# lcdadapter.net
KiCad netlist of a schematic drawn in EAGLE
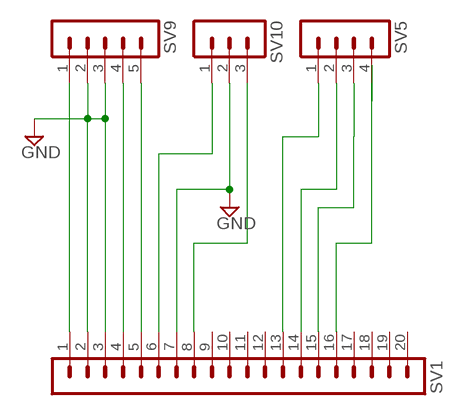
[diagram p0: schematic, sheet 1]

(export (version "E")
  (design (tool "Eeschema 10.0.6"))
  (components
    (comp (ref "SV1")
      (value "MA20-1L")
      (footprint "eagle-import:MA20-1L")
      (libsource (lib "eagle-import") (part "MA20-1L"))
    )
    (comp (ref "SV5")
      (value "MA04-1")
      (footprint "eagle-import:MA04-1")
      (libsource (lib "eagle-import") (part "MA04-1"))
    )
    (comp (ref "SV9")
      (value "MA05-1")
      (footprint "eagle-import:MA05-1")
      (libsource (lib "eagle-import") (part "MA05-1"))
    )
    (comp (ref "SV10")
      (value "MA03-1")
      (footprint "eagle-import:MA03-1")
      (libsource (lib "eagle-import") (part "MA03-1"))
    )
  )
  (nets
    (net (code "1") (name "GND") (class "Default")
      (node (ref "SV1") (pin "2") (pinfunction "2_2") (pintype "passive"))
      (node (ref "SV1") (pin "3") (pinfunction "3_3") (pintype "passive"))
      (node (ref "SV1") (pin "7") (pinfunction "7_7") (pintype "passive"))
      (node (ref "SV10") (pin "2") (pinfunction "2_2") (pintype "passive"))
      (node (ref "SV9") (pin "2") (pinfunction "2_2") (pintype "passive"))
      (node (ref "SV9") (pin "3") (pinfunction "3_3") (pintype "passive"))
    )
    (net (code "2") (name "Net-(SV1-Pad1)") (class "Default")
      (node (ref "SV1") (pin "1") (pinfunction "1_1") (pintype "passive"))
      (node (ref "SV9") (pin "1") (pinfunction "1_1") (pintype "passive"))
    )
    (net (code "3") (name "Net-(SV1-Pad4)") (class "Default")
      (node (ref "SV1") (pin "4") (pinfunction "4_4") (pintype "passive"))
      (node (ref "SV9") (pin "4") (pinfunction "4_4") (pintype "passive"))
    )
    (net (code "4") (name "Net-(SV1-Pad5)") (class "Default")
      (node (ref "SV1") (pin "5") (pinfunction "5_5") (pintype "passive"))
      (node (ref "SV9") (pin "5") (pinfunction "5_5") (pintype "passive"))
    )
    (net (code "5") (name "Net-(SV1-Pad6)") (class "Default")
      (node (ref "SV1") (pin "6") (pinfunction "6_6") (pintype "passive"))
      (node (ref "SV10") (pin "1") (pinfunction "1_1") (pintype "passive"))
    )
    (net (code "6") (name "Net-(SV1-Pad8)") (class "Default")
      (node (ref "SV1") (pin "8") (pinfunction "8_8") (pintype "passive"))
      (node (ref "SV10") (pin "3") (pinfunction "3_3") (pintype "passive"))
    )
    (net (code "7") (name "Net-(SV1-Pad13)") (class "Default")
      (node (ref "SV1") (pin "13") (pinfunction "13_13") (pintype "passive"))
      (node (ref "SV5") (pin "1") (pinfunction "1_1") (pintype "passive"))
    )
    (net (code "8") (name "Net-(SV1-Pad14)") (class "Default")
      (node (ref "SV1") (pin "14") (pinfunction "14_14") (pintype "passive"))
      (node (ref "SV5") (pin "2") (pinfunction "2_2") (pintype "passive"))
    )
    (net (code "9") (name "Net-(SV1-Pad15)") (class "Default")
      (node (ref "SV1") (pin "15") (pinfunction "15_15") (pintype "passive"))
      (node (ref "SV5") (pin "3") (pinfunction "3_3") (pintype "passive"))
    )
    (net (code "10") (name "Net-(SV1-Pad16)") (class "Default")
      (node (ref "SV1") (pin "16") (pinfunction "16_16") (pintype "passive"))
      (node (ref "SV5") (pin "4") (pinfunction "4_4") (pintype "passive"))
    )
    (net (code "11") (name "unconnected-(SV1-Pad9)") (class "Default")
      (node (ref "SV1") (pin "9") (pinfunction "9_9") (pintype "passive"))
    )
    (net (code "12") (name "unconnected-(SV1-Pad10)") (class "Default")
      (node (ref "SV1") (pin "10") (pinfunction "10_10") (pintype "passive"))
    )
    (net (code "13") (name "unconnected-(SV1-Pad11)") (class "Default")
      (node (ref "SV1") (pin "11") (pinfunction "11_11") (pintype "passive"))
    )
    (net (code "14") (name "unconnected-(SV1-Pad12)") (class "Default")
      (node (ref "SV1") (pin "12") (pinfunction "12_12") (pintype "passive"))
    )
    (net (code "15") (name "unconnected-(SV1-Pad17)") (class "Default")
      (node (ref "SV1") (pin "17") (pinfunction "17_17") (pintype "passive"))
    )
    (net (code "16") (name "unconnected-(SV1-Pad18)") (class "Default")
      (node (ref "SV1") (pin "18") (pinfunction "18_18") (pintype "passive"))
    )
    (net (code "17") (name "unconnected-(SV1-Pad19)") (class "Default")
      (node (ref "SV1") (pin "19") (pinfunction "19_19") (pintype "passive"))
    )
    (net (code "18") (name "unconnected-(SV1-Pad20)") (class "Default")
      (node (ref "SV1") (pin "20") (pinfunction "20_20") (pintype "passive"))
    )
  )
)
